# placa_final.net
KiCad netlist of a schematic drawn in EAGLE
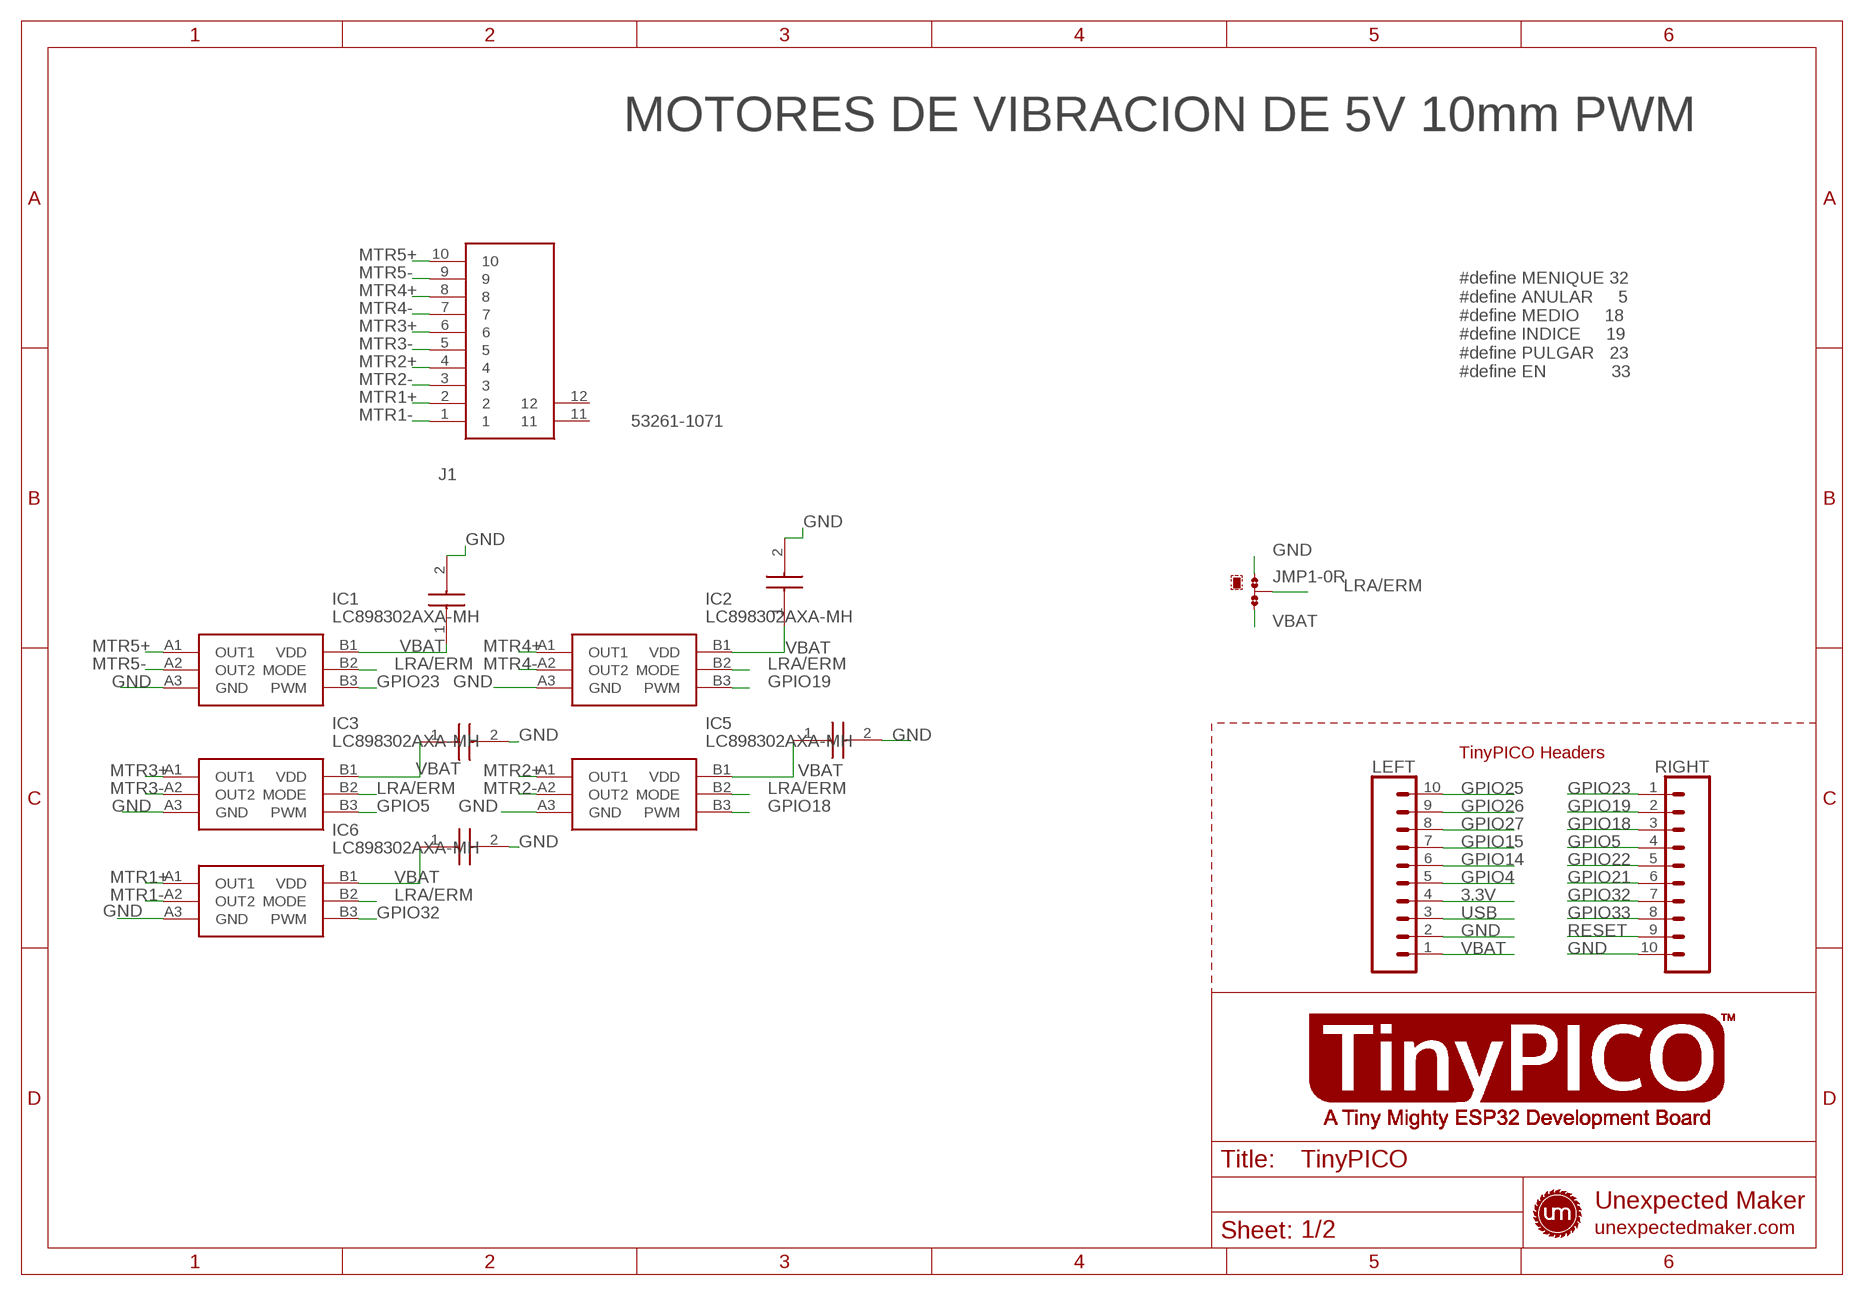
[diagram p0: schematic, sheet 1]
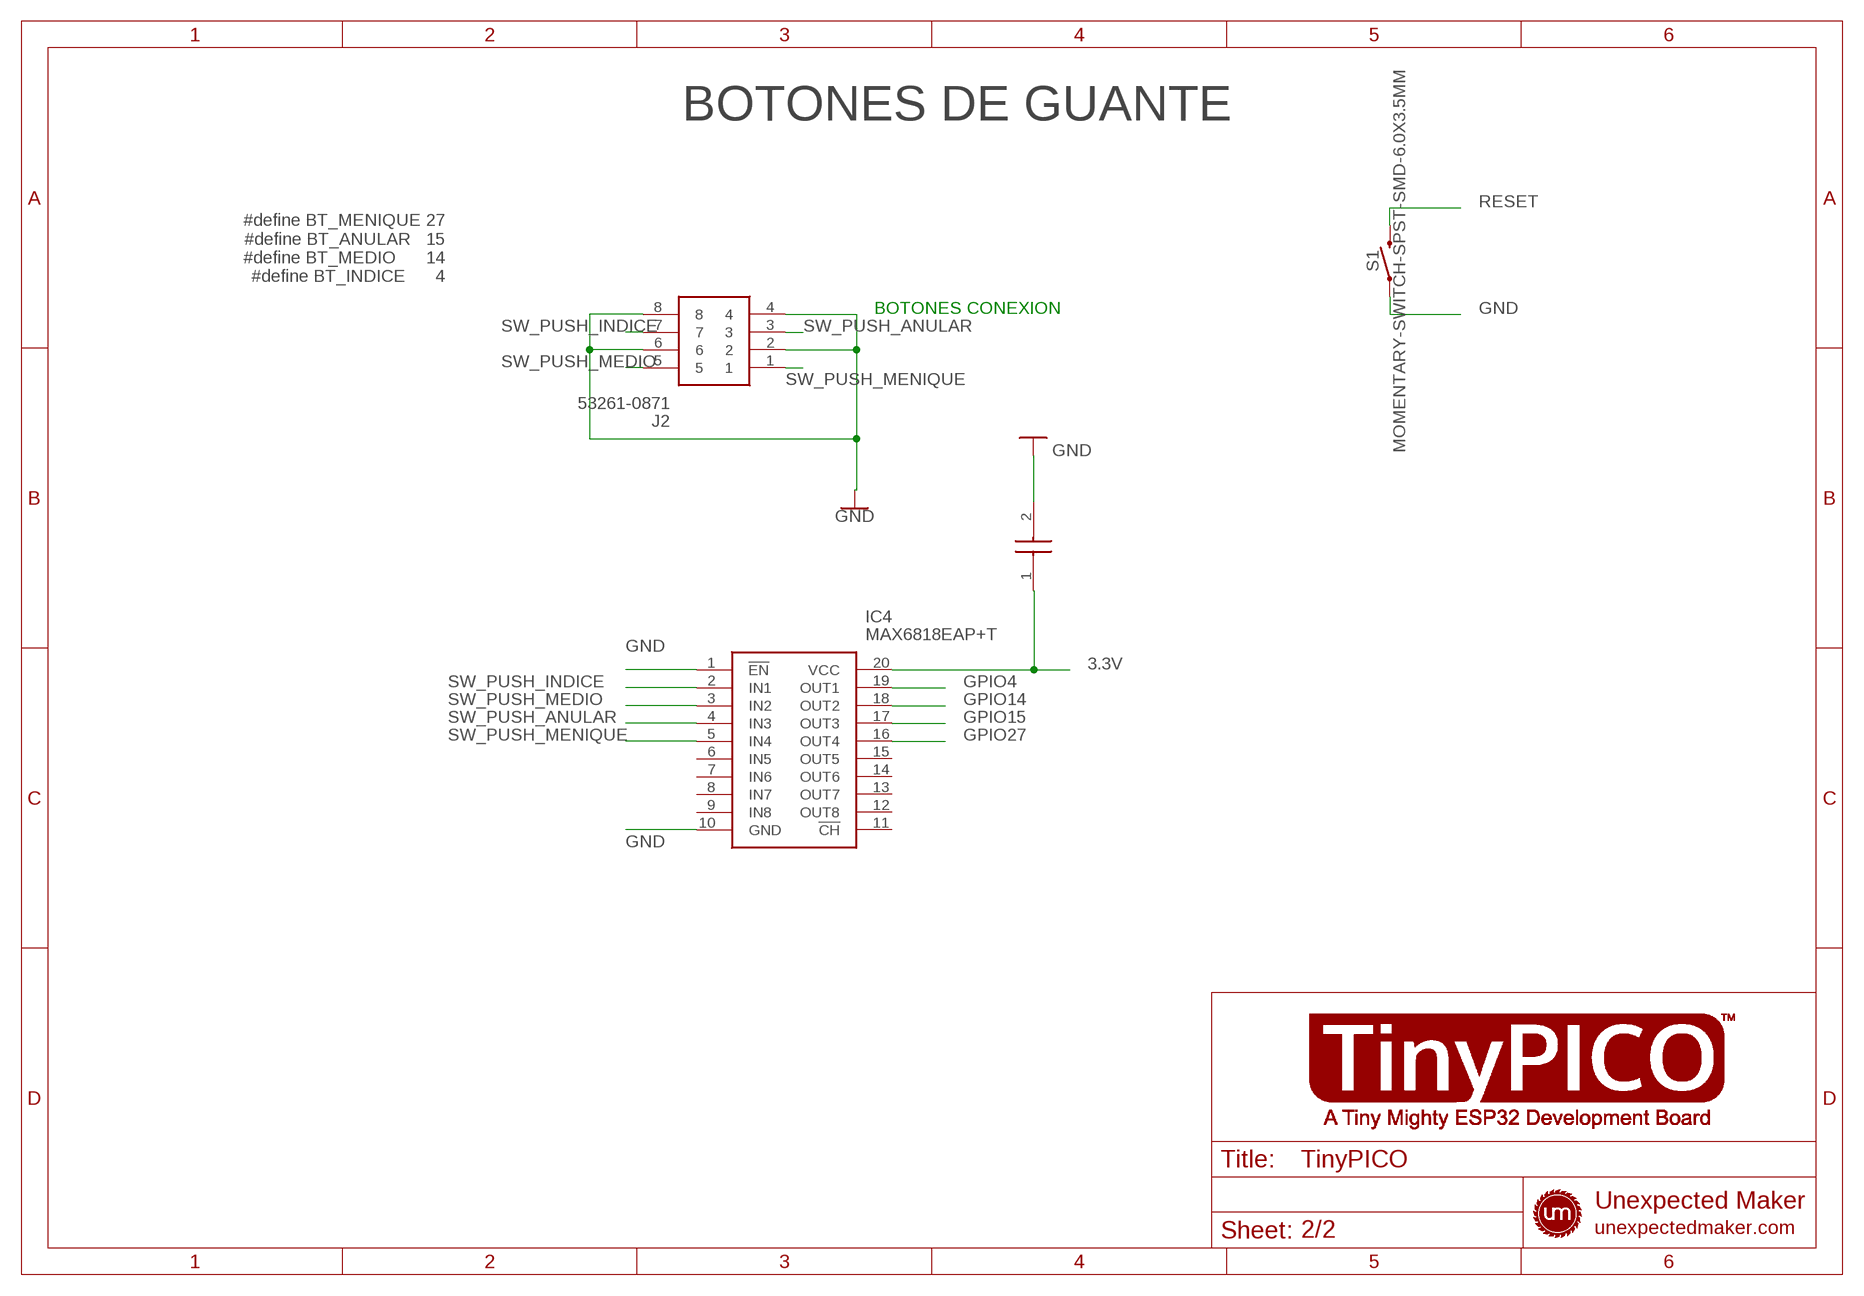
[diagram p1: schematic, sheet 2]

(export (version "E")
  (design (tool "Eeschema 10.0.6"))
  (components
    (comp (ref "C8")
      (value "0603B104K160CT")
      (footprint "eagle-import:CAPC1608X87N")
      (fields (field (name "MOUSER_PART_NUMBER") "791-0603B104K160CT"))
      (libsource (lib "eagle-import") (part "0603B104K160CT"))
    )
    (comp (ref "IC4")
      (value "MAX6818EAP+T")
      (footprint "eagle-import:SOP65P778X199-20N")
      (fields (field (name "MOUSER_PART_NUMBER") "700-MAX6818EAPT"))
      (libsource (lib "eagle-import") (part "MAX6818EAP+T"))
    )
    (comp (ref "J2")
      (value "53261-0871")
      (footprint "eagle-import:53261-0871")
      (fields (field (name "MOUSER_PART_NUMBER") "538-53261-0871"))
      (libsource (lib "eagle-import") (part "53261-0871"))
    )
    (comp (ref "S1")
      (value "MOMENTARY-SWITCH-SPST-SMD-6.0X3.5MM")
      (footprint "eagle-import:TACTILE_SWITCH_SMD_6.0X3.5MM")
      (libsource (lib "eagle-import") (part "MOMENTARY-SWITCH-SPST-SMD-6.0X3.5MM"))
    )
    (comp (ref "C1")
      (value "0603B104K160CT")
      (footprint "eagle-import:CAPC1608X87N")
      (fields (field (name "MOUSER_PART_NUMBER") "791-0603B104K160CT"))
      (libsource (lib "eagle-import") (part "0603B104K160CT"))
    )
    (comp (ref "C2")
      (value "0603B104K160CT")
      (footprint "eagle-import:CAPC1608X87N")
      (fields (field (name "MOUSER_PART_NUMBER") "791-0603B104K160CT"))
      (libsource (lib "eagle-import") (part "0603B104K160CT"))
    )
    (comp (ref "C3")
      (value "0603B104K160CT")
      (footprint "eagle-import:CAPC1608X87N")
      (fields (field (name "MOUSER_PART_NUMBER") "791-0603B104K160CT"))
      (libsource (lib "eagle-import") (part "0603B104K160CT"))
    )
    (comp (ref "C4")
      (value "0603B104K160CT")
      (footprint "eagle-import:CAPC1608X87N")
      (fields (field (name "MOUSER_PART_NUMBER") "791-0603B104K160CT"))
      (libsource (lib "eagle-import") (part "0603B104K160CT"))
    )
    (comp (ref "C5")
      (value "0603B104K160CT")
      (footprint "eagle-import:CAPC1608X87N")
      (fields (field (name "MOUSER_PART_NUMBER") "791-0603B104K160CT"))
      (libsource (lib "eagle-import") (part "0603B104K160CT"))
    )
    (comp (ref "IC1")
      (value "LC898302AXA-MH")
      (footprint "eagle-import:BGA6C40P3X2_118X78X65")
      (fields (field (name "MOUSER_PART_NUMBER") "863-LC898302AXA-MH"))
      (libsource (lib "eagle-import") (part "LC898302AXA-MH"))
    )
    (comp (ref "IC2")
      (value "LC898302AXA-MH")
      (footprint "eagle-import:BGA6C40P3X2_118X78X65")
      (fields (field (name "MOUSER_PART_NUMBER") "863-LC898302AXA-MH"))
      (libsource (lib "eagle-import") (part "LC898302AXA-MH"))
    )
    (comp (ref "IC3")
      (value "LC898302AXA-MH")
      (footprint "eagle-import:BGA6C40P3X2_118X78X65")
      (fields (field (name "MOUSER_PART_NUMBER") "863-LC898302AXA-MH"))
      (libsource (lib "eagle-import") (part "LC898302AXA-MH"))
    )
    (comp (ref "IC5")
      (value "LC898302AXA-MH")
      (footprint "eagle-import:BGA6C40P3X2_118X78X65")
      (fields (field (name "MOUSER_PART_NUMBER") "863-LC898302AXA-MH"))
      (libsource (lib "eagle-import") (part "LC898302AXA-MH"))
    )
    (comp (ref "IC6")
      (value "LC898302AXA-MH")
      (footprint "eagle-import:BGA6C40P3X2_118X78X65")
      (fields (field (name "MOUSER_PART_NUMBER") "863-LC898302AXA-MH"))
      (libsource (lib "eagle-import") (part "LC898302AXA-MH"))
    )
    (comp (ref "J1")
      (value "53261-1071")
      (footprint "eagle-import:532611071")
      (fields (field (name "MOUSER_PART_NUMBER") "538-53261-1071"))
      (libsource (lib "eagle-import") (part "53261-1071"))
    )
    (comp (ref "JMP1")
      (value "0R-JUMPA")
      (footprint "eagle-import:A0R-JMP")
      (libsource (lib "eagle-import") (part "0R-JUMPA"))
    )
    (comp (ref "LEFT")
      (value "TINYPICO_HEADER_10NO_SILK_PTH_FEMALE")
      (footprint "eagle-import:1X10_NO_SILK")
      (libsource (lib "eagle-import") (part "TINYPICO_HEADER_10NO_SILK_PTH_FEMALE"))
    )
    (comp (ref "RIGHT")
      (value "TINYPICO_HEADER_10NO_SILK_PTH_FEMALE")
      (footprint "eagle-import:1X10_NO_SILK")
      (libsource (lib "eagle-import") (part "TINYPICO_HEADER_10NO_SILK_PTH_FEMALE"))
    )
  )
  (nets
    (net (code "1") (name "3.3V") (class "Default")
      (node (ref "C8") (pin "1") (pinfunction "1_1") (pintype "bidirectional"))
      (node (ref "IC4") (pin "20") (pinfunction "VCC_20") (pintype "power_in"))
      (node (ref "LEFT") (pin "4") (pinfunction "4_4") (pintype "passive"))
    )
    (net (code "2") (name "GND") (class "Default")
      (node (ref "C1") (pin "2") (pinfunction "2_2") (pintype "bidirectional"))
      (node (ref "C2") (pin "2") (pinfunction "2_2") (pintype "bidirectional"))
      (node (ref "C3") (pin "2") (pinfunction "2_2") (pintype "bidirectional"))
      (node (ref "C4") (pin "2") (pinfunction "2_2") (pintype "bidirectional"))
      (node (ref "C5") (pin "2") (pinfunction "2_2") (pintype "bidirectional"))
      (node (ref "C8") (pin "2") (pinfunction "2_2") (pintype "bidirectional"))
      (node (ref "IC1") (pin "A3") (pinfunction "GND_A3") (pintype "bidirectional"))
      (node (ref "IC2") (pin "A3") (pinfunction "GND_A3") (pintype "bidirectional"))
      (node (ref "IC3") (pin "A3") (pinfunction "GND_A3") (pintype "bidirectional"))
      (node (ref "IC4") (pin "1") (pinfunction "~{EN}_1") (pintype "input"))
      (node (ref "IC4") (pin "10") (pinfunction "GND_10") (pintype "power_in"))
      (node (ref "IC5") (pin "A3") (pinfunction "GND_A3") (pintype "bidirectional"))
      (node (ref "IC6") (pin "A3") (pinfunction "GND_A3") (pintype "bidirectional"))
      (node (ref "J2") (pin "2") (pinfunction "2_2") (pintype "bidirectional"))
      (node (ref "J2") (pin "4") (pinfunction "4_4") (pintype "bidirectional"))
      (node (ref "J2") (pin "6") (pinfunction "6_6") (pintype "bidirectional"))
      (node (ref "J2") (pin "8") (pinfunction "8_8") (pintype "bidirectional"))
      (node (ref "JMP1") (pin "1") (pinfunction "1_1") (pintype "passive"))
      (node (ref "LEFT") (pin "2") (pinfunction "2_2") (pintype "passive"))
      (node (ref "RIGHT") (pin "10") (pinfunction "10_10") (pintype "passive"))
      (node (ref "S1") (pin "1") (pinfunction "1_1") (pintype "passive"))
    )
    (net (code "3") (name "GPIO4") (class "Default")
      (node (ref "IC4") (pin "19") (pinfunction "OUT1_19") (pintype "output"))
      (node (ref "LEFT") (pin "5") (pinfunction "5_5") (pintype "passive"))
    )
    (net (code "4") (name "GPIO5") (class "Default")
      (node (ref "IC3") (pin "B3") (pinfunction "PWM_B3") (pintype "bidirectional"))
      (node (ref "RIGHT") (pin "4") (pinfunction "4_4") (pintype "passive"))
    )
    (net (code "5") (name "GPIO14") (class "Default")
      (node (ref "IC4") (pin "18") (pinfunction "OUT2_18") (pintype "output"))
      (node (ref "LEFT") (pin "6") (pinfunction "6_6") (pintype "passive"))
    )
    (net (code "6") (name "GPIO15") (class "Default")
      (node (ref "IC4") (pin "17") (pinfunction "OUT3_17") (pintype "output"))
      (node (ref "LEFT") (pin "7") (pinfunction "7_7") (pintype "passive"))
    )
    (net (code "7") (name "GPIO18") (class "Default")
      (node (ref "IC5") (pin "B3") (pinfunction "PWM_B3") (pintype "bidirectional"))
      (node (ref "RIGHT") (pin "3") (pinfunction "3_3") (pintype "passive"))
    )
    (net (code "8") (name "GPIO19") (class "Default")
      (node (ref "IC2") (pin "B3") (pinfunction "PWM_B3") (pintype "bidirectional"))
      (node (ref "RIGHT") (pin "2") (pinfunction "2_2") (pintype "passive"))
    )
    (net (code "9") (name "GPIO21") (class "Default")
      (node (ref "RIGHT") (pin "6") (pinfunction "6_6") (pintype "passive"))
    )
    (net (code "10") (name "GPIO22") (class "Default")
      (node (ref "RIGHT") (pin "5") (pinfunction "5_5") (pintype "passive"))
    )
    (net (code "11") (name "GPIO23") (class "Default")
      (node (ref "IC1") (pin "B3") (pinfunction "PWM_B3") (pintype "bidirectional"))
      (node (ref "RIGHT") (pin "1") (pinfunction "1_1") (pintype "passive"))
    )
    (net (code "12") (name "GPIO25") (class "Default")
      (node (ref "LEFT") (pin "10") (pinfunction "10_10") (pintype "passive"))
    )
    (net (code "13") (name "GPIO26") (class "Default")
      (node (ref "LEFT") (pin "9") (pinfunction "9_9") (pintype "passive"))
    )
    (net (code "14") (name "GPIO27") (class "Default")
      (node (ref "IC4") (pin "16") (pinfunction "OUT4_16") (pintype "output"))
      (node (ref "LEFT") (pin "8") (pinfunction "8_8") (pintype "passive"))
    )
    (net (code "15") (name "GPIO32") (class "Default")
      (node (ref "IC6") (pin "B3") (pinfunction "PWM_B3") (pintype "bidirectional"))
      (node (ref "RIGHT") (pin "7") (pinfunction "7_7") (pintype "passive"))
    )
    (net (code "16") (name "GPIO33") (class "Default")
      (node (ref "RIGHT") (pin "8") (pinfunction "8_8") (pintype "passive"))
    )
    (net (code "17") (name "LRA{slash}ERM") (class "Default")
      (node (ref "IC1") (pin "B2") (pinfunction "MODE_B2") (pintype "bidirectional"))
      (node (ref "IC2") (pin "B2") (pinfunction "MODE_B2") (pintype "bidirectional"))
      (node (ref "IC3") (pin "B2") (pinfunction "MODE_B2") (pintype "bidirectional"))
      (node (ref "IC5") (pin "B2") (pinfunction "MODE_B2") (pintype "bidirectional"))
      (node (ref "IC6") (pin "B2") (pinfunction "MODE_B2") (pintype "bidirectional"))
      (node (ref "JMP1") (pin "2") (pinfunction "2_2") (pintype "passive"))
    )
    (net (code "18") (name "MTR1+") (class "Default")
      (node (ref "IC6") (pin "A1") (pinfunction "OUT1_A1") (pintype "bidirectional"))
      (node (ref "J1") (pin "2") (pinfunction "2_2") (pintype "bidirectional"))
    )
    (net (code "19") (name "MTR1-") (class "Default")
      (node (ref "IC6") (pin "A2") (pinfunction "OUT2_A2") (pintype "bidirectional"))
      (node (ref "J1") (pin "1") (pinfunction "1_1") (pintype "bidirectional"))
    )
    (net (code "20") (name "MTR2+") (class "Default")
      (node (ref "IC5") (pin "A1") (pinfunction "OUT1_A1") (pintype "bidirectional"))
      (node (ref "J1") (pin "4") (pinfunction "4_4") (pintype "bidirectional"))
    )
    (net (code "21") (name "MTR2-") (class "Default")
      (node (ref "IC5") (pin "A2") (pinfunction "OUT2_A2") (pintype "bidirectional"))
      (node (ref "J1") (pin "3") (pinfunction "3_3") (pintype "bidirectional"))
    )
    (net (code "22") (name "MTR3+") (class "Default")
      (node (ref "IC3") (pin "A1") (pinfunction "OUT1_A1") (pintype "bidirectional"))
      (node (ref "J1") (pin "6") (pinfunction "6_6") (pintype "bidirectional"))
    )
    (net (code "23") (name "MTR3-") (class "Default")
      (node (ref "IC3") (pin "A2") (pinfunction "OUT2_A2") (pintype "bidirectional"))
      (node (ref "J1") (pin "5") (pinfunction "5_5") (pintype "bidirectional"))
    )
    (net (code "24") (name "MTR4+") (class "Default")
      (node (ref "IC2") (pin "A1") (pinfunction "OUT1_A1") (pintype "bidirectional"))
      (node (ref "J1") (pin "8") (pinfunction "8_8") (pintype "bidirectional"))
    )
    (net (code "25") (name "MTR4-") (class "Default")
      (node (ref "IC2") (pin "A2") (pinfunction "OUT2_A2") (pintype "bidirectional"))
      (node (ref "J1") (pin "7") (pinfunction "7_7") (pintype "bidirectional"))
    )
    (net (code "26") (name "MTR5+") (class "Default")
      (node (ref "IC1") (pin "A1") (pinfunction "OUT1_A1") (pintype "bidirectional"))
      (node (ref "J1") (pin "10") (pinfunction "10_10") (pintype "bidirectional"))
    )
    (net (code "27") (name "MTR5-") (class "Default")
      (node (ref "IC1") (pin "A2") (pinfunction "OUT2_A2") (pintype "bidirectional"))
      (node (ref "J1") (pin "9") (pinfunction "9_9") (pintype "bidirectional"))
    )
    (net (code "28") (name "RESET") (class "Default")
      (node (ref "RIGHT") (pin "9") (pinfunction "9_9") (pintype "passive"))
      (node (ref "S1") (pin "2") (pinfunction "2_2") (pintype "passive"))
    )
    (net (code "29") (name "SW_PUSH_ANULAR") (class "Default")
      (node (ref "IC4") (pin "4") (pinfunction "IN3_4") (pintype "input"))
      (node (ref "J2") (pin "3") (pinfunction "3_3") (pintype "bidirectional"))
    )
    (net (code "30") (name "SW_PUSH_INDICE") (class "Default")
      (node (ref "IC4") (pin "2") (pinfunction "IN1_2") (pintype "input"))
      (node (ref "J2") (pin "7") (pinfunction "7_7") (pintype "bidirectional"))
    )
    (net (code "31") (name "SW_PUSH_MEDIO") (class "Default")
      (node (ref "IC4") (pin "3") (pinfunction "IN2_3") (pintype "input"))
      (node (ref "J2") (pin "5") (pinfunction "5_5") (pintype "bidirectional"))
    )
    (net (code "32") (name "SW_PUSH_MENIQUE") (class "Default")
      (node (ref "IC4") (pin "5") (pinfunction "IN4_5") (pintype "input"))
      (node (ref "J2") (pin "1") (pinfunction "1_1") (pintype "bidirectional"))
    )
    (net (code "33") (name "USB") (class "Default")
      (node (ref "LEFT") (pin "3") (pinfunction "3_3") (pintype "passive"))
    )
    (net (code "34") (name "VBAT") (class "Default")
      (node (ref "C1") (pin "1") (pinfunction "1_1") (pintype "bidirectional"))
      (node (ref "C2") (pin "1") (pinfunction "1_1") (pintype "bidirectional"))
      (node (ref "C3") (pin "1") (pinfunction "1_1") (pintype "bidirectional"))
      (node (ref "C4") (pin "1") (pinfunction "1_1") (pintype "bidirectional"))
      (node (ref "C5") (pin "1") (pinfunction "1_1") (pintype "bidirectional"))
      (node (ref "IC1") (pin "B1") (pinfunction "VDD_B1") (pintype "bidirectional"))
      (node (ref "IC2") (pin "B1") (pinfunction "VDD_B1") (pintype "bidirectional"))
      (node (ref "IC3") (pin "B1") (pinfunction "VDD_B1") (pintype "bidirectional"))
      (node (ref "IC5") (pin "B1") (pinfunction "VDD_B1") (pintype "bidirectional"))
      (node (ref "IC6") (pin "B1") (pinfunction "VDD_B1") (pintype "bidirectional"))
      (node (ref "JMP1") (pin "3") (pinfunction "3_3") (pintype "passive"))
      (node (ref "LEFT") (pin "1") (pinfunction "1_1") (pintype "passive"))
    )
    (net (code "35") (name "unconnected-(IC4-IN5-Pad6)") (class "Default")
      (node (ref "IC4") (pin "6") (pinfunction "IN5_6") (pintype "input"))
    )
    (net (code "36") (name "unconnected-(IC4-IN6-Pad7)") (class "Default")
      (node (ref "IC4") (pin "7") (pinfunction "IN6_7") (pintype "input"))
    )
    (net (code "37") (name "unconnected-(IC4-IN7-Pad8)") (class "Default")
      (node (ref "IC4") (pin "8") (pinfunction "IN7_8") (pintype "input"))
    )
    (net (code "38") (name "unconnected-(IC4-IN8-Pad9)") (class "Default")
      (node (ref "IC4") (pin "9") (pinfunction "IN8_9") (pintype "input"))
    )
    (net (code "39") (name "unconnected-(IC4-OUT5-Pad15)") (class "Default")
      (node (ref "IC4") (pin "15") (pinfunction "OUT5_15") (pintype "output"))
    )
    (net (code "40") (name "unconnected-(IC4-OUT6-Pad14)") (class "Default")
      (node (ref "IC4") (pin "14") (pinfunction "OUT6_14") (pintype "output"))
    )
    (net (code "41") (name "unconnected-(IC4-OUT7-Pad13)") (class "Default")
      (node (ref "IC4") (pin "13") (pinfunction "OUT7_13") (pintype "output"))
    )
    (net (code "42") (name "unconnected-(IC4-OUT8-Pad12)") (class "Default")
      (node (ref "IC4") (pin "12") (pinfunction "OUT8_12") (pintype "output"))
    )
    (net (code "43") (name "unconnected-(IC4-~{CH}-Pad11)") (class "Default")
      (node (ref "IC4") (pin "11") (pinfunction "~{CH}_11") (pintype "output"))
    )
    (net (code "44") (name "unconnected-(J1-Pad11)") (class "Default")
      (node (ref "J1") (pin "11") (pinfunction "11_11") (pintype "bidirectional"))
    )
    (net (code "45") (name "unconnected-(J1-Pad12)") (class "Default")
      (node (ref "J1") (pin "12") (pinfunction "12_12") (pintype "bidirectional"))
    )
  )
)
